# snc98_Display_15x7-Seg_3-digit_LTD056.net
KiCad netlist of a schematic drawn in EAGLE
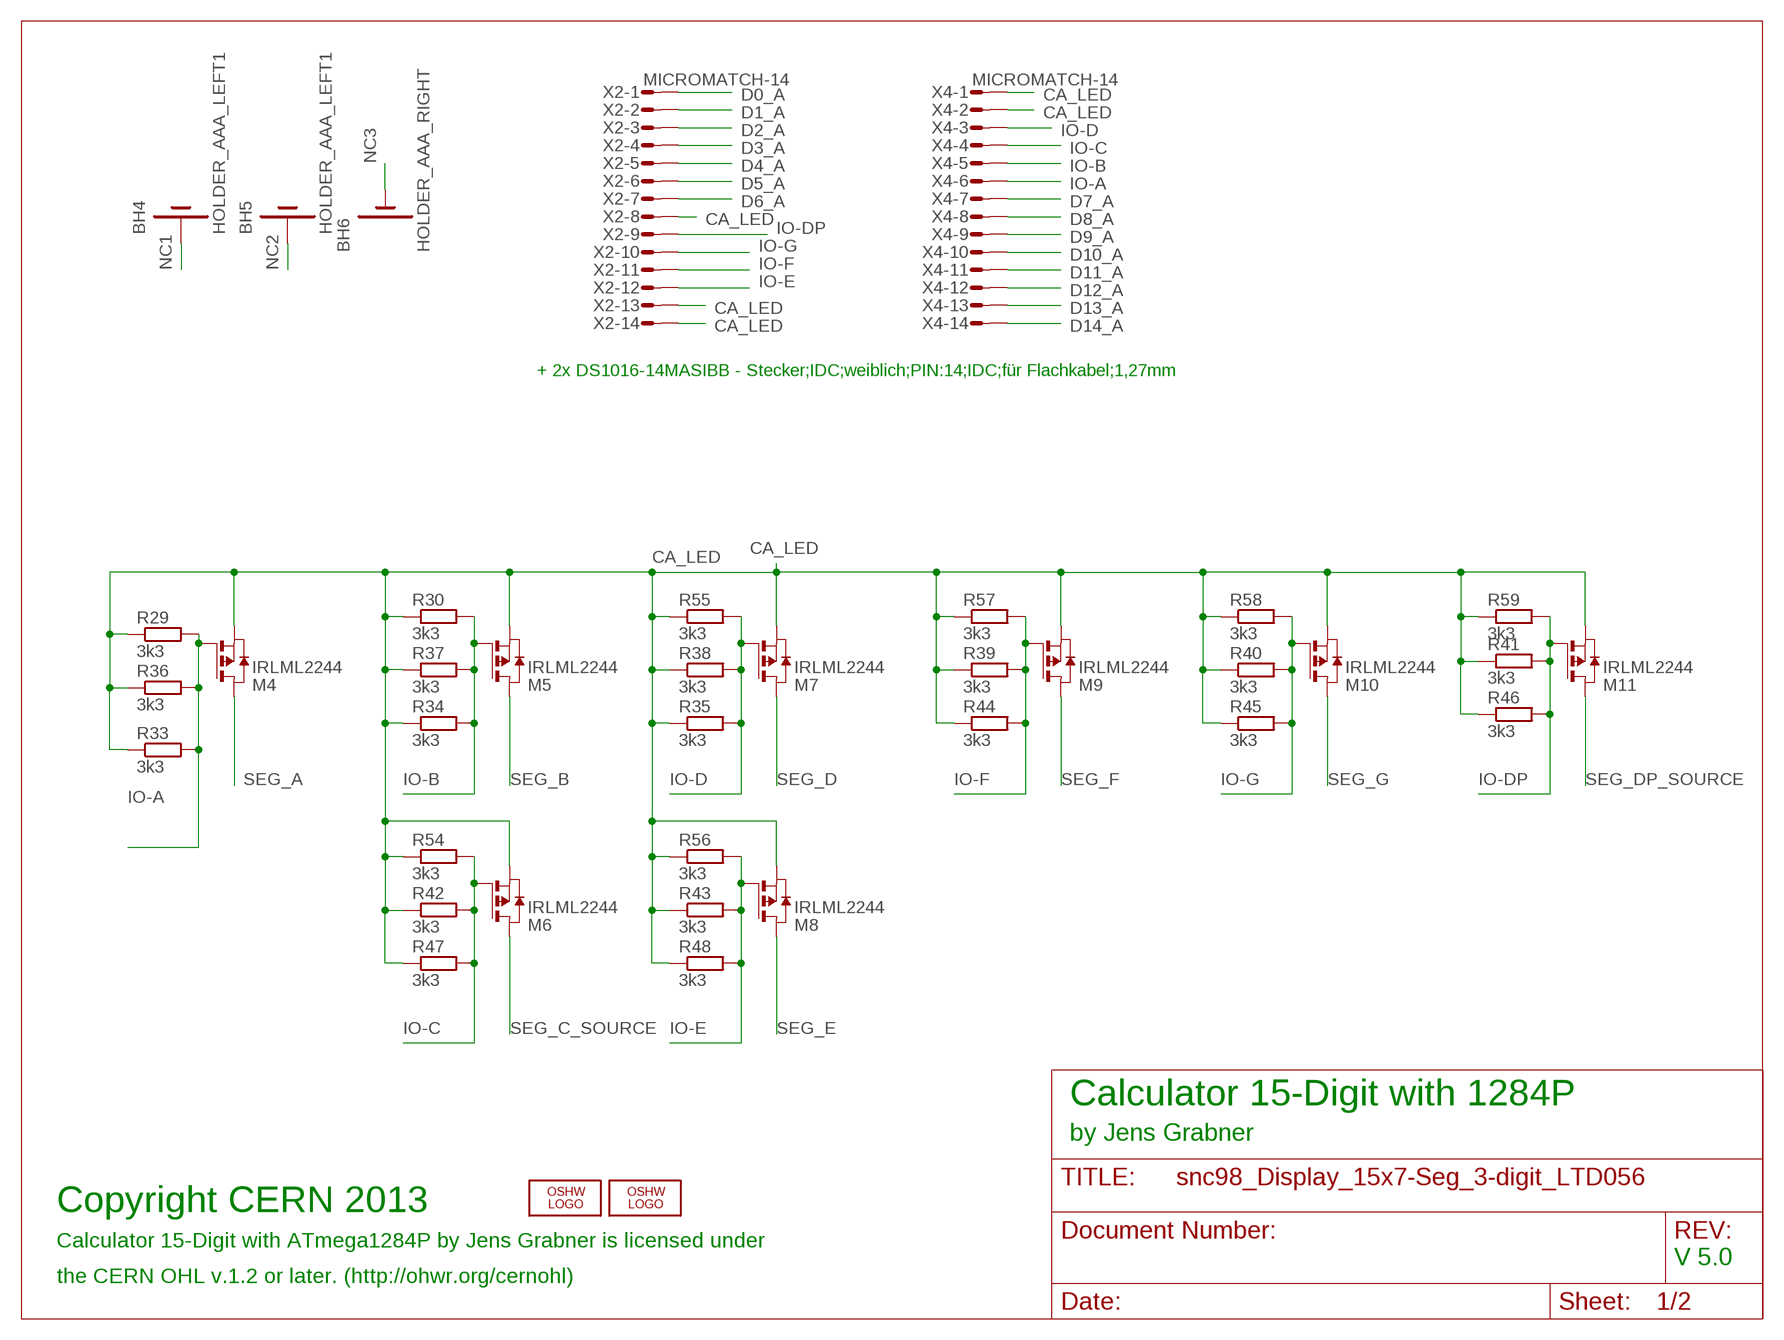
[diagram p0: schematic, sheet 1]
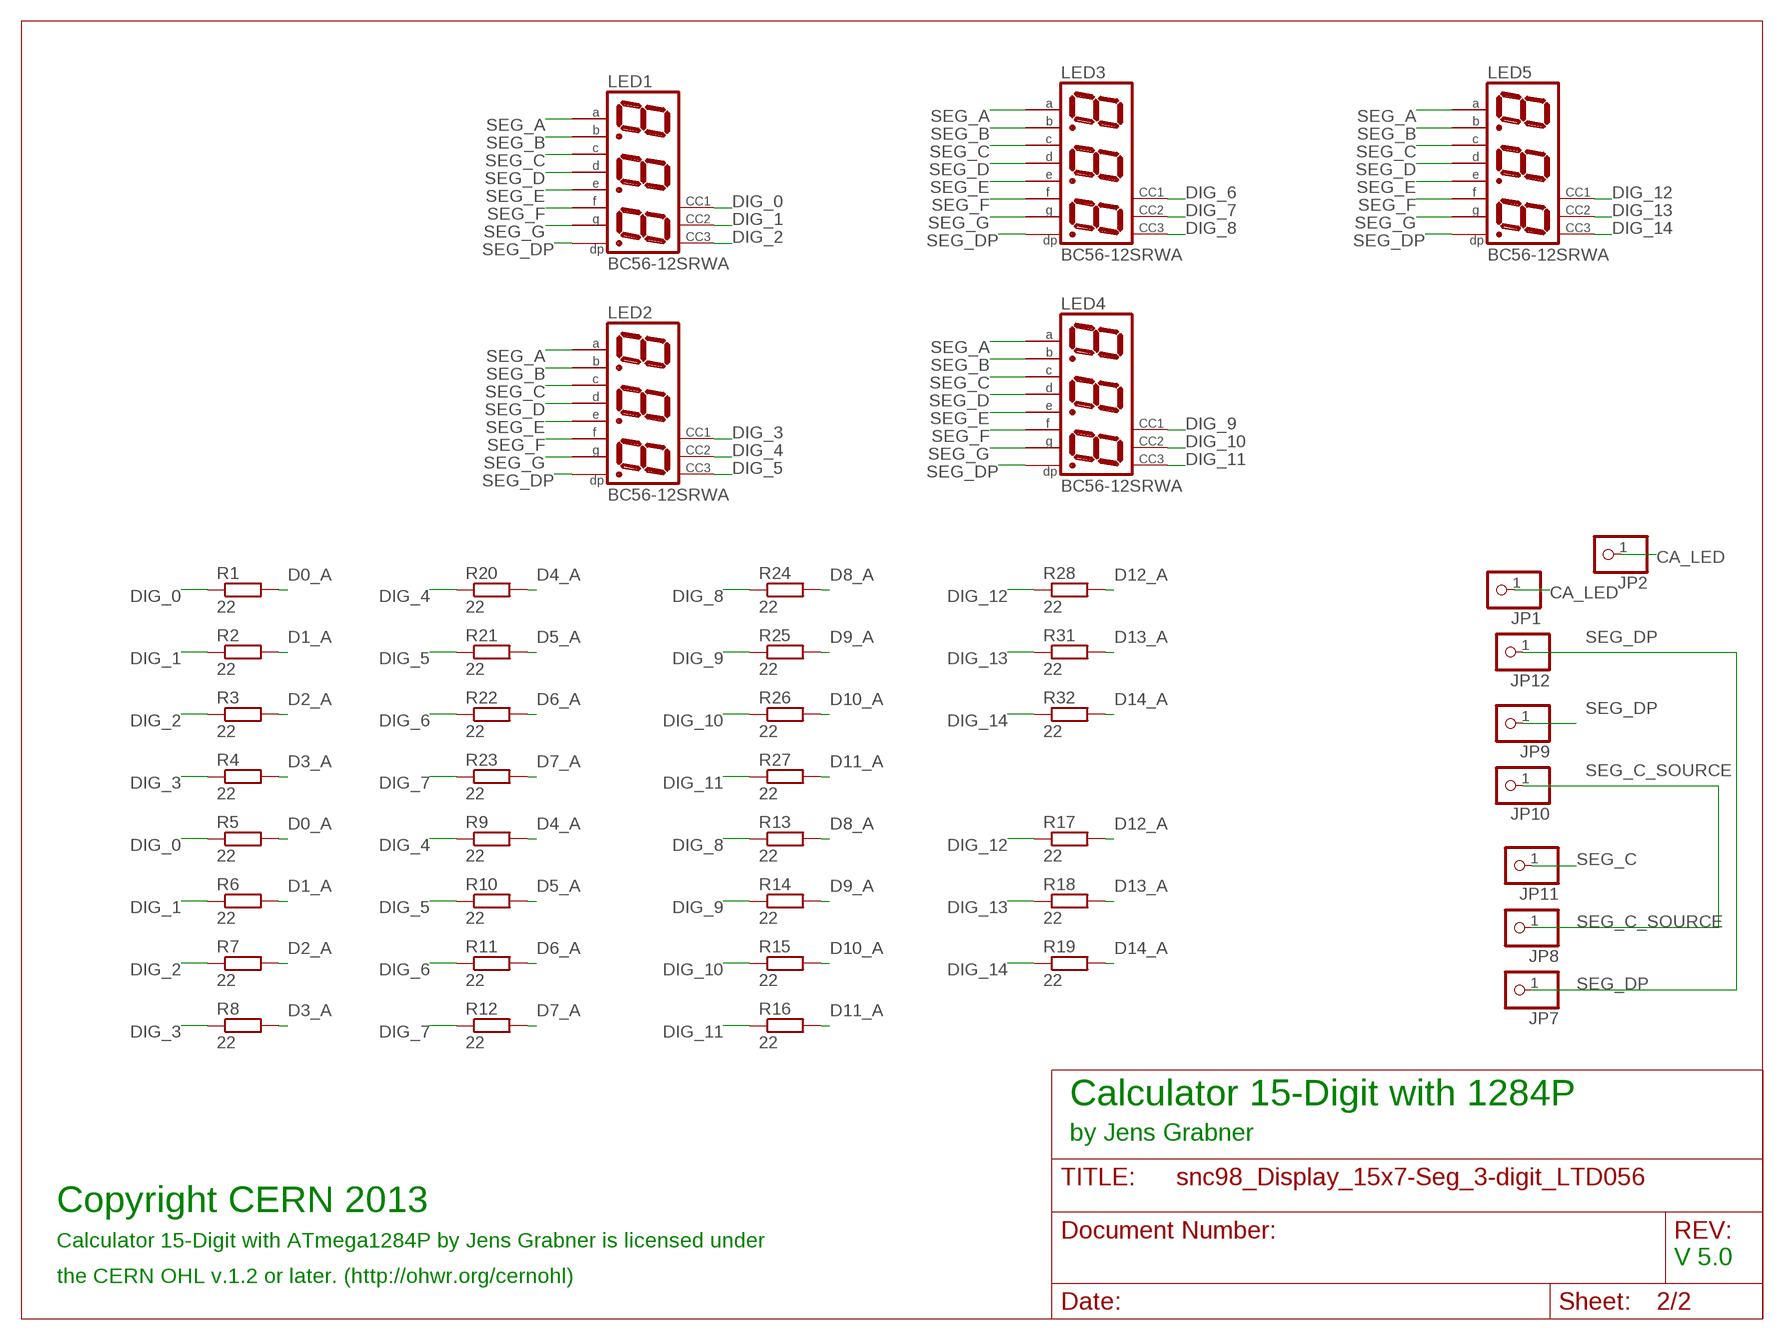
[diagram p1: schematic, sheet 2]

(export (version "E")
  (design (tool "Eeschema 10.0.6"))
  (components
    (comp (ref "JP1")
      (value "PINHD-1X1")
      (footprint "eagle-import:1X01")
      (libsource (lib "eagle-import") (part "PINHD-1X1"))
    )
    (comp (ref "JP2")
      (value "PINHD-1X1")
      (footprint "eagle-import:1X01")
      (libsource (lib "eagle-import") (part "PINHD-1X1"))
    )
    (comp (ref "JP7")
      (value "PINHD-1X1")
      (footprint "eagle-import:1X01")
      (libsource (lib "eagle-import") (part "PINHD-1X1"))
    )
    (comp (ref "JP8")
      (value "PINHD-1X1")
      (footprint "eagle-import:1X01")
      (libsource (lib "eagle-import") (part "PINHD-1X1"))
    )
    (comp (ref "JP9")
      (value "PINHD-1X1")
      (footprint "eagle-import:1X01")
      (libsource (lib "eagle-import") (part "PINHD-1X1"))
    )
    (comp (ref "JP10")
      (value "PINHD-1X1")
      (footprint "eagle-import:1X01")
      (libsource (lib "eagle-import") (part "PINHD-1X1"))
    )
    (comp (ref "JP11")
      (value "PINHD-1X1")
      (footprint "eagle-import:1X01")
      (libsource (lib "eagle-import") (part "PINHD-1X1"))
    )
    (comp (ref "JP12")
      (value "PINHD-1X1")
      (footprint "eagle-import:1X01")
      (libsource (lib "eagle-import") (part "PINHD-1X1"))
    )
    (comp (ref "LED1")
      (value "BC56-12SRWA")
      (footprint "eagle-import:BX56-12")
      (libsource (lib "eagle-import") (part "B?56-12WACSR"))
    )
    (comp (ref "LED2")
      (value "BC56-12SRWA")
      (footprint "eagle-import:BX56-12")
      (libsource (lib "eagle-import") (part "B?56-12WACSR"))
    )
    (comp (ref "LED3")
      (value "BC56-12SRWA")
      (footprint "eagle-import:BX56-12")
      (libsource (lib "eagle-import") (part "B?56-12WACSR"))
    )
    (comp (ref "LED4")
      (value "BC56-12SRWA")
      (footprint "eagle-import:BX56-12")
      (libsource (lib "eagle-import") (part "B?56-12WACSR"))
    )
    (comp (ref "LED5")
      (value "BC56-12SRWA")
      (footprint "eagle-import:BX56-12")
      (libsource (lib "eagle-import") (part "B?56-12WACSR"))
    )
    (comp (ref "R1")
      (value "22")
      (footprint "eagle-import:R0805")
      (libsource (lib "eagle-import") (part "R-EU_R0805"))
    )
    (comp (ref "R2")
      (value "22")
      (footprint "eagle-import:R0805")
      (libsource (lib "eagle-import") (part "R-EU_R0805"))
    )
    (comp (ref "R3")
      (value "22")
      (footprint "eagle-import:R0805")
      (libsource (lib "eagle-import") (part "R-EU_R0805"))
    )
    (comp (ref "R4")
      (value "22")
      (footprint "eagle-import:R0805")
      (libsource (lib "eagle-import") (part "R-EU_R0805"))
    )
    (comp (ref "R5")
      (value "22")
      (footprint "eagle-import:R1210")
      (libsource (lib "eagle-import") (part "R-EU_R1210"))
    )
    (comp (ref "R6")
      (value "22")
      (footprint "eagle-import:R1210")
      (libsource (lib "eagle-import") (part "R-EU_R1210"))
    )
    (comp (ref "R7")
      (value "22")
      (footprint "eagle-import:R1210")
      (libsource (lib "eagle-import") (part "R-EU_R1210"))
    )
    (comp (ref "R8")
      (value "22")
      (footprint "eagle-import:R1210")
      (libsource (lib "eagle-import") (part "R-EU_R1210"))
    )
    (comp (ref "R9")
      (value "22")
      (footprint "eagle-import:R1210")
      (libsource (lib "eagle-import") (part "R-EU_R1210"))
    )
    (comp (ref "R10")
      (value "22")
      (footprint "eagle-import:R1210")
      (libsource (lib "eagle-import") (part "R-EU_R1210"))
    )
    (comp (ref "R11")
      (value "22")
      (footprint "eagle-import:R1210")
      (libsource (lib "eagle-import") (part "R-EU_R1210"))
    )
    (comp (ref "R12")
      (value "22")
      (footprint "eagle-import:R1210")
      (libsource (lib "eagle-import") (part "R-EU_R1210"))
    )
    (comp (ref "R13")
      (value "22")
      (footprint "eagle-import:R1210")
      (libsource (lib "eagle-import") (part "R-EU_R1210"))
    )
    (comp (ref "R14")
      (value "22")
      (footprint "eagle-import:R1210")
      (libsource (lib "eagle-import") (part "R-EU_R1210"))
    )
    (comp (ref "R15")
      (value "22")
      (footprint "eagle-import:R1210")
      (libsource (lib "eagle-import") (part "R-EU_R1210"))
    )
    (comp (ref "R16")
      (value "22")
      (footprint "eagle-import:R1210")
      (libsource (lib "eagle-import") (part "R-EU_R1210"))
    )
    (comp (ref "R17")
      (value "22")
      (footprint "eagle-import:R1210")
      (libsource (lib "eagle-import") (part "R-EU_R1210"))
    )
    (comp (ref "R18")
      (value "22")
      (footprint "eagle-import:R1210")
      (libsource (lib "eagle-import") (part "R-EU_R1210"))
    )
    (comp (ref "R19")
      (value "22")
      (footprint "eagle-import:R1210")
      (libsource (lib "eagle-import") (part "R-EU_R1210"))
    )
    (comp (ref "R20")
      (value "22")
      (footprint "eagle-import:R0805")
      (libsource (lib "eagle-import") (part "R-EU_R0805"))
    )
    (comp (ref "R21")
      (value "22")
      (footprint "eagle-import:R0805")
      (libsource (lib "eagle-import") (part "R-EU_R0805"))
    )
    (comp (ref "R22")
      (value "22")
      (footprint "eagle-import:R0805")
      (libsource (lib "eagle-import") (part "R-EU_R0805"))
    )
    (comp (ref "R23")
      (value "22")
      (footprint "eagle-import:R0805")
      (libsource (lib "eagle-import") (part "R-EU_R0805"))
    )
    (comp (ref "R24")
      (value "22")
      (footprint "eagle-import:R0805")
      (libsource (lib "eagle-import") (part "R-EU_R0805"))
    )
    (comp (ref "R25")
      (value "22")
      (footprint "eagle-import:R0805")
      (libsource (lib "eagle-import") (part "R-EU_R0805"))
    )
    (comp (ref "R26")
      (value "22")
      (footprint "eagle-import:R0805")
      (libsource (lib "eagle-import") (part "R-EU_R0805"))
    )
    (comp (ref "R27")
      (value "22")
      (footprint "eagle-import:R0805")
      (libsource (lib "eagle-import") (part "R-EU_R0805"))
    )
    (comp (ref "R28")
      (value "22")
      (footprint "eagle-import:R0805")
      (libsource (lib "eagle-import") (part "R-EU_R0805"))
    )
    (comp (ref "R31")
      (value "22")
      (footprint "eagle-import:R0805")
      (libsource (lib "eagle-import") (part "R-EU_R0805"))
    )
    (comp (ref "R32")
      (value "22")
      (footprint "eagle-import:R0805")
      (libsource (lib "eagle-import") (part "R-EU_R0805"))
    )
    (comp (ref "BH4")
      (value "HOLDER_AAA_LEFT1")
      (footprint "eagle-import:BATTERY-AAA-LEFT")
      (libsource (lib "eagle-import") (part "HOLDER_AAA_LEFT1"))
    )
    (comp (ref "BH5")
      (value "HOLDER_AAA_LEFT1")
      (footprint "eagle-import:BATTERY-AAA-LEFT")
      (libsource (lib "eagle-import") (part "HOLDER_AAA_LEFT1"))
    )
    (comp (ref "BH6")
      (value "HOLDER_AAA_RIGHT")
      (footprint "eagle-import:BATTERY-AAA-RIGHT")
      (libsource (lib "eagle-import") (part "HOLDER_AAA_RIGHT"))
    )
    (comp (ref "LOGO1")
      (value "OSHW_LOGO_8MILX0150-NT")
      (footprint "eagle-import:OSHW_8X150_NOTEXT")
      (libsource (lib "eagle-import") (part "OSHW_LOGO_8MILX0150-NT"))
    )
    (comp (ref "LOGO3")
      (value "OSHW_LOGO_6MILX0100-NT")
      (footprint "eagle-import:OSHW_6X100_NOTEXT")
      (libsource (lib "eagle-import") (part "OSHW_LOGO_6MILX0100-NT"))
    )
    (comp (ref "M4")
      (value "IRLML2244")
      (footprint "eagle-import:SOT-23")
      (fields (field (name "MF") "INFINEON") (field (name "MPN") "IRLML2244TRPBF"))
      (libsource (lib "eagle-import") (part "IRLML6402"))
    )
    (comp (ref "M5")
      (value "IRLML2244")
      (footprint "eagle-import:SOT-23")
      (fields (field (name "MF") "INFINEON") (field (name "MPN") "IRLML2244TRPBF"))
      (libsource (lib "eagle-import") (part "IRLML6402"))
    )
    (comp (ref "M6")
      (value "IRLML2244")
      (footprint "eagle-import:SOT-23")
      (fields (field (name "MF") "INFINEON") (field (name "MPN") "IRLML2244TRPBF"))
      (libsource (lib "eagle-import") (part "IRLML6402"))
    )
    (comp (ref "M7")
      (value "IRLML2244")
      (footprint "eagle-import:SOT-23")
      (fields (field (name "MF") "INFINEON") (field (name "MPN") "IRLML2244TRPBF"))
      (libsource (lib "eagle-import") (part "IRLML6402"))
    )
    (comp (ref "M8")
      (value "IRLML2244")
      (footprint "eagle-import:SOT-23")
      (fields (field (name "MF") "INFINEON") (field (name "MPN") "IRLML2244TRPBF"))
      (libsource (lib "eagle-import") (part "IRLML6402"))
    )
    (comp (ref "M9")
      (value "IRLML2244")
      (footprint "eagle-import:SOT-23")
      (fields (field (name "MF") "INFINEON") (field (name "MPN") "IRLML2244TRPBF"))
      (libsource (lib "eagle-import") (part "IRLML6402"))
    )
    (comp (ref "M10")
      (value "IRLML2244")
      (footprint "eagle-import:SOT-23")
      (fields (field (name "MF") "INFINEON") (field (name "MPN") "IRLML2244TRPBF"))
      (libsource (lib "eagle-import") (part "IRLML6402"))
    )
    (comp (ref "M11")
      (value "IRLML2244")
      (footprint "eagle-import:SOT-23")
      (fields (field (name "MF") "INFINEON") (field (name "MPN") "IRLML2244TRPBF"))
      (libsource (lib "eagle-import") (part "IRLML6402"))
    )
    (comp (ref "R29")
      (value "3k3")
      (footprint "eagle-import:0204_5")
      (libsource (lib "eagle-import") (part "R-EU_0204/5"))
    )
    (comp (ref "R30")
      (value "3k3")
      (footprint "eagle-import:0204_5")
      (libsource (lib "eagle-import") (part "R-EU_0204/5"))
    )
    (comp (ref "R33")
      (value "3k3")
      (footprint "eagle-import:M0805")
      (libsource (lib "eagle-import") (part "R-EU_M0805"))
    )
    (comp (ref "R34")
      (value "3k3")
      (footprint "eagle-import:M0805")
      (libsource (lib "eagle-import") (part "R-EU_M0805"))
    )
    (comp (ref "R35")
      (value "3k3")
      (footprint "eagle-import:M0805")
      (libsource (lib "eagle-import") (part "R-EU_M0805"))
    )
    (comp (ref "R36")
      (value "3k3")
      (footprint "eagle-import:R1206")
      (libsource (lib "eagle-import") (part "R-EU_R1206"))
    )
    (comp (ref "R37")
      (value "3k3")
      (footprint "eagle-import:R1206")
      (libsource (lib "eagle-import") (part "R-EU_R1206"))
    )
    (comp (ref "R38")
      (value "3k3")
      (footprint "eagle-import:R1206")
      (libsource (lib "eagle-import") (part "R-EU_R1206"))
    )
    (comp (ref "R39")
      (value "3k3")
      (footprint "eagle-import:R1206")
      (libsource (lib "eagle-import") (part "R-EU_R1206"))
    )
    (comp (ref "R40")
      (value "3k3")
      (footprint "eagle-import:R1206")
      (libsource (lib "eagle-import") (part "R-EU_R1206"))
    )
    (comp (ref "R41")
      (value "3k3")
      (footprint "eagle-import:R1206")
      (libsource (lib "eagle-import") (part "R-EU_R1206"))
    )
    (comp (ref "R42")
      (value "3k3")
      (footprint "eagle-import:R1206")
      (libsource (lib "eagle-import") (part "R-EU_R1206"))
    )
    (comp (ref "R43")
      (value "3k3")
      (footprint "eagle-import:R1206")
      (libsource (lib "eagle-import") (part "R-EU_R1206"))
    )
    (comp (ref "R44")
      (value "3k3")
      (footprint "eagle-import:M0805")
      (libsource (lib "eagle-import") (part "R-EU_M0805"))
    )
    (comp (ref "R45")
      (value "3k3")
      (footprint "eagle-import:M0805")
      (libsource (lib "eagle-import") (part "R-EU_M0805"))
    )
    (comp (ref "R46")
      (value "3k3")
      (footprint "eagle-import:M0805")
      (libsource (lib "eagle-import") (part "R-EU_M0805"))
    )
    (comp (ref "R47")
      (value "3k3")
      (footprint "eagle-import:M0805")
      (libsource (lib "eagle-import") (part "R-EU_M0805"))
    )
    (comp (ref "R48")
      (value "3k3")
      (footprint "eagle-import:M0805")
      (libsource (lib "eagle-import") (part "R-EU_M0805"))
    )
    (comp (ref "R54")
      (value "3k3")
      (footprint "eagle-import:0204_5")
      (libsource (lib "eagle-import") (part "R-EU_0204/5"))
    )
    (comp (ref "R55")
      (value "3k3")
      (footprint "eagle-import:0204_5")
      (libsource (lib "eagle-import") (part "R-EU_0204/5"))
    )
    (comp (ref "R56")
      (value "3k3")
      (footprint "eagle-import:0204_5")
      (libsource (lib "eagle-import") (part "R-EU_0204/5"))
    )
    (comp (ref "R57")
      (value "3k3")
      (footprint "eagle-import:0204_5")
      (libsource (lib "eagle-import") (part "R-EU_0204/5"))
    )
    (comp (ref "R58")
      (value "3k3")
      (footprint "eagle-import:0204_5")
      (libsource (lib "eagle-import") (part "R-EU_0204/5"))
    )
    (comp (ref "R59")
      (value "3k3")
      (footprint "eagle-import:0204_5")
      (libsource (lib "eagle-import") (part "R-EU_0204/5"))
    )
    (comp (ref "X2")
      (value "MICROMATCH-14")
      (footprint "eagle-import:MICROMATCH-14")
      (fields
        (field (name "MF") "FARNELL")
        (field (name "MPN") "8-215464-4")
        (field (name "MF_1") "AMP - TE CONNECTIVITY")
      )
      (libsource (lib "eagle-import") (part "MICROMATCH-14"))
    )
    (comp (ref "X4")
      (value "MICROMATCH-14")
      (footprint "eagle-import:MICROMATCH-14")
      (fields
        (field (name "MF") "FARNELL")
        (field (name "MPN") "8-215464-4")
        (field (name "MF_1") "AMP - TE CONNECTIVITY")
      )
      (libsource (lib "eagle-import") (part "MICROMATCH-14"))
    )
  )
  (nets
    (net (code "1") (name "CA_LED") (class "Default")
      (node (ref "JP1") (pin "1") (pinfunction "1_1") (pintype "passive"))
      (node (ref "JP2") (pin "1") (pinfunction "1_1") (pintype "passive"))
      (node (ref "M10") (pin "2") (pinfunction "S_2") (pintype "passive"))
      (node (ref "M11") (pin "2") (pinfunction "S_2") (pintype "passive"))
      (node (ref "M4") (pin "2") (pinfunction "S_2") (pintype "passive"))
      (node (ref "M5") (pin "2") (pinfunction "S_2") (pintype "passive"))
      (node (ref "M6") (pin "2") (pinfunction "S_2") (pintype "passive"))
      (node (ref "M7") (pin "2") (pinfunction "S_2") (pintype "passive"))
      (node (ref "M8") (pin "2") (pinfunction "S_2") (pintype "passive"))
      (node (ref "M9") (pin "2") (pinfunction "S_2") (pintype "passive"))
      (node (ref "R29") (pin "1") (pinfunction "1_1") (pintype "passive"))
      (node (ref "R30") (pin "1") (pinfunction "1_1") (pintype "passive"))
      (node (ref "R33") (pin "1") (pinfunction "1_1") (pintype "passive"))
      (node (ref "R34") (pin "1") (pinfunction "1_1") (pintype "passive"))
      (node (ref "R35") (pin "1") (pinfunction "1_1") (pintype "passive"))
      (node (ref "R36") (pin "1") (pinfunction "1_1") (pintype "passive"))
      (node (ref "R37") (pin "1") (pinfunction "1_1") (pintype "passive"))
      (node (ref "R38") (pin "1") (pinfunction "1_1") (pintype "passive"))
      (node (ref "R39") (pin "1") (pinfunction "1_1") (pintype "passive"))
      (node (ref "R40") (pin "1") (pinfunction "1_1") (pintype "passive"))
      (node (ref "R41") (pin "1") (pinfunction "1_1") (pintype "passive"))
      (node (ref "R42") (pin "1") (pinfunction "1_1") (pintype "passive"))
      (node (ref "R43") (pin "1") (pinfunction "1_1") (pintype "passive"))
      (node (ref "R44") (pin "1") (pinfunction "1_1") (pintype "passive"))
      (node (ref "R45") (pin "1") (pinfunction "1_1") (pintype "passive"))
      (node (ref "R46") (pin "1") (pinfunction "1_1") (pintype "passive"))
      (node (ref "R47") (pin "1") (pinfunction "1_1") (pintype "passive"))
      (node (ref "R48") (pin "1") (pinfunction "1_1") (pintype "passive"))
      (node (ref "R54") (pin "1") (pinfunction "1_1") (pintype "passive"))
      (node (ref "R55") (pin "1") (pinfunction "1_1") (pintype "passive"))
      (node (ref "R56") (pin "1") (pinfunction "1_1") (pintype "passive"))
      (node (ref "R57") (pin "1") (pinfunction "1_1") (pintype "passive"))
      (node (ref "R58") (pin "1") (pinfunction "1_1") (pintype "passive"))
      (node (ref "R59") (pin "1") (pinfunction "1_1") (pintype "passive"))
      (node (ref "X2") (pin "13") (pinfunction "S_13") (pintype "passive"))
      (node (ref "X2") (pin "14") (pinfunction "S_14") (pintype "passive"))
      (node (ref "X2") (pin "8") (pinfunction "S_8") (pintype "passive"))
      (node (ref "X4") (pin "1") (pinfunction "S_1") (pintype "passive"))
      (node (ref "X4") (pin "2") (pinfunction "S_2") (pintype "passive"))
    )
    (net (code "2") (name "D0_A") (class "Default")
      (node (ref "R1") (pin "2") (pinfunction "2_2") (pintype "passive"))
      (node (ref "R5") (pin "2") (pinfunction "2_2") (pintype "passive"))
      (node (ref "X2") (pin "1") (pinfunction "S_1") (pintype "passive"))
    )
    (net (code "3") (name "D1_A") (class "Default")
      (node (ref "R2") (pin "2") (pinfunction "2_2") (pintype "passive"))
      (node (ref "R6") (pin "2") (pinfunction "2_2") (pintype "passive"))
      (node (ref "X2") (pin "2") (pinfunction "S_2") (pintype "passive"))
    )
    (net (code "4") (name "D2_A") (class "Default")
      (node (ref "R3") (pin "2") (pinfunction "2_2") (pintype "passive"))
      (node (ref "R7") (pin "2") (pinfunction "2_2") (pintype "passive"))
      (node (ref "X2") (pin "3") (pinfunction "S_3") (pintype "passive"))
    )
    (net (code "5") (name "D3_A") (class "Default")
      (node (ref "R4") (pin "2") (pinfunction "2_2") (pintype "passive"))
      (node (ref "R8") (pin "2") (pinfunction "2_2") (pintype "passive"))
      (node (ref "X2") (pin "4") (pinfunction "S_4") (pintype "passive"))
    )
    (net (code "6") (name "D4_A") (class "Default")
      (node (ref "R20") (pin "2") (pinfunction "2_2") (pintype "passive"))
      (node (ref "R9") (pin "2") (pinfunction "2_2") (pintype "passive"))
      (node (ref "X2") (pin "5") (pinfunction "S_5") (pintype "passive"))
    )
    (net (code "7") (name "D5_A") (class "Default")
      (node (ref "R10") (pin "2") (pinfunction "2_2") (pintype "passive"))
      (node (ref "R21") (pin "2") (pinfunction "2_2") (pintype "passive"))
      (node (ref "X2") (pin "6") (pinfunction "S_6") (pintype "passive"))
    )
    (net (code "8") (name "D6_A") (class "Default")
      (node (ref "R11") (pin "2") (pinfunction "2_2") (pintype "passive"))
      (node (ref "R22") (pin "2") (pinfunction "2_2") (pintype "passive"))
      (node (ref "X2") (pin "7") (pinfunction "S_7") (pintype "passive"))
    )
    (net (code "9") (name "D7_A") (class "Default")
      (node (ref "R12") (pin "2") (pinfunction "2_2") (pintype "passive"))
      (node (ref "R23") (pin "2") (pinfunction "2_2") (pintype "passive"))
      (node (ref "X4") (pin "7") (pinfunction "S_7") (pintype "passive"))
    )
    (net (code "10") (name "D8_A") (class "Default")
      (node (ref "R13") (pin "2") (pinfunction "2_2") (pintype "passive"))
      (node (ref "R24") (pin "2") (pinfunction "2_2") (pintype "passive"))
      (node (ref "X4") (pin "8") (pinfunction "S_8") (pintype "passive"))
    )
    (net (code "11") (name "D9_A") (class "Default")
      (node (ref "R14") (pin "2") (pinfunction "2_2") (pintype "passive"))
      (node (ref "R25") (pin "2") (pinfunction "2_2") (pintype "passive"))
      (node (ref "X4") (pin "9") (pinfunction "S_9") (pintype "passive"))
    )
    (net (code "12") (name "D10_A") (class "Default")
      (node (ref "R15") (pin "2") (pinfunction "2_2") (pintype "passive"))
      (node (ref "R26") (pin "2") (pinfunction "2_2") (pintype "passive"))
      (node (ref "X4") (pin "10") (pinfunction "S_10") (pintype "passive"))
    )
    (net (code "13") (name "D11_A") (class "Default")
      (node (ref "R16") (pin "2") (pinfunction "2_2") (pintype "passive"))
      (node (ref "R27") (pin "2") (pinfunction "2_2") (pintype "passive"))
      (node (ref "X4") (pin "11") (pinfunction "S_11") (pintype "passive"))
    )
    (net (code "14") (name "D12_A") (class "Default")
      (node (ref "R17") (pin "2") (pinfunction "2_2") (pintype "passive"))
      (node (ref "R28") (pin "2") (pinfunction "2_2") (pintype "passive"))
      (node (ref "X4") (pin "12") (pinfunction "S_12") (pintype "passive"))
    )
    (net (code "15") (name "D13_A") (class "Default")
      (node (ref "R18") (pin "2") (pinfunction "2_2") (pintype "passive"))
      (node (ref "R31") (pin "2") (pinfunction "2_2") (pintype "passive"))
      (node (ref "X4") (pin "13") (pinfunction "S_13") (pintype "passive"))
    )
    (net (code "16") (name "D14_A") (class "Default")
      (node (ref "R19") (pin "2") (pinfunction "2_2") (pintype "passive"))
      (node (ref "R32") (pin "2") (pinfunction "2_2") (pintype "passive"))
      (node (ref "X4") (pin "14") (pinfunction "S_14") (pintype "passive"))
    )
    (net (code "17") (name "DIG_0") (class "Default")
      (node (ref "LED1") (pin "12") (pinfunction "CA_12") (pintype "passive"))
      (node (ref "R1") (pin "1") (pinfunction "1_1") (pintype "passive"))
      (node (ref "R5") (pin "1") (pinfunction "1_1") (pintype "passive"))
    )
    (net (code "18") (name "DIG_1") (class "Default")
      (node (ref "LED1") (pin "9") (pinfunction "CA_9") (pintype "passive"))
      (node (ref "R2") (pin "1") (pinfunction "1_1") (pintype "passive"))
      (node (ref "R6") (pin "1") (pinfunction "1_1") (pintype "passive"))
    )
    (net (code "19") (name "DIG_2") (class "Default")
      (node (ref "LED1") (pin "8") (pinfunction "CA_8") (pintype "passive"))
      (node (ref "R3") (pin "1") (pinfunction "1_1") (pintype "passive"))
      (node (ref "R7") (pin "1") (pinfunction "1_1") (pintype "passive"))
    )
    (net (code "20") (name "DIG_3") (class "Default")
      (node (ref "LED2") (pin "12") (pinfunction "CA_12") (pintype "passive"))
      (node (ref "R4") (pin "1") (pinfunction "1_1") (pintype "passive"))
      (node (ref "R8") (pin "1") (pinfunction "1_1") (pintype "passive"))
    )
    (net (code "21") (name "DIG_4") (class "Default")
      (node (ref "LED2") (pin "9") (pinfunction "CA_9") (pintype "passive"))
      (node (ref "R20") (pin "1") (pinfunction "1_1") (pintype "passive"))
      (node (ref "R9") (pin "1") (pinfunction "1_1") (pintype "passive"))
    )
    (net (code "22") (name "DIG_5") (class "Default")
      (node (ref "LED2") (pin "8") (pinfunction "CA_8") (pintype "passive"))
      (node (ref "R10") (pin "1") (pinfunction "1_1") (pintype "passive"))
      (node (ref "R21") (pin "1") (pinfunction "1_1") (pintype "passive"))
    )
    (net (code "23") (name "DIG_6") (class "Default")
      (node (ref "LED3") (pin "12") (pinfunction "CA_12") (pintype "passive"))
      (node (ref "R11") (pin "1") (pinfunction "1_1") (pintype "passive"))
      (node (ref "R22") (pin "1") (pinfunction "1_1") (pintype "passive"))
    )
    (net (code "24") (name "DIG_7") (class "Default")
      (node (ref "LED3") (pin "9") (pinfunction "CA_9") (pintype "passive"))
      (node (ref "R12") (pin "1") (pinfunction "1_1") (pintype "passive"))
      (node (ref "R23") (pin "1") (pinfunction "1_1") (pintype "passive"))
    )
    (net (code "25") (name "DIG_8") (class "Default")
      (node (ref "LED3") (pin "8") (pinfunction "CA_8") (pintype "passive"))
      (node (ref "R13") (pin "1") (pinfunction "1_1") (pintype "passive"))
      (node (ref "R24") (pin "1") (pinfunction "1_1") (pintype "passive"))
    )
    (net (code "26") (name "DIG_9") (class "Default")
      (node (ref "LED4") (pin "12") (pinfunction "CA_12") (pintype "passive"))
      (node (ref "R14") (pin "1") (pinfunction "1_1") (pintype "passive"))
      (node (ref "R25") (pin "1") (pinfunction "1_1") (pintype "passive"))
    )
    (net (code "27") (name "DIG_10") (class "Default")
      (node (ref "LED4") (pin "9") (pinfunction "CA_9") (pintype "passive"))
      (node (ref "R15") (pin "1") (pinfunction "1_1") (pintype "passive"))
      (node (ref "R26") (pin "1") (pinfunction "1_1") (pintype "passive"))
    )
    (net (code "28") (name "DIG_11") (class "Default")
      (node (ref "LED4") (pin "8") (pinfunction "CA_8") (pintype "passive"))
      (node (ref "R16") (pin "1") (pinfunction "1_1") (pintype "passive"))
      (node (ref "R27") (pin "1") (pinfunction "1_1") (pintype "passive"))
    )
    (net (code "29") (name "DIG_12") (class "Default")
      (node (ref "LED5") (pin "12") (pinfunction "CA_12") (pintype "passive"))
      (node (ref "R17") (pin "1") (pinfunction "1_1") (pintype "passive"))
      (node (ref "R28") (pin "1") (pinfunction "1_1") (pintype "passive"))
    )
    (net (code "30") (name "DIG_13") (class "Default")
      (node (ref "LED5") (pin "9") (pinfunction "CA_9") (pintype "passive"))
      (node (ref "R18") (pin "1") (pinfunction "1_1") (pintype "passive"))
      (node (ref "R31") (pin "1") (pinfunction "1_1") (pintype "passive"))
    )
    (net (code "31") (name "DIG_14") (class "Default")
      (node (ref "LED5") (pin "8") (pinfunction "CA_8") (pintype "passive"))
      (node (ref "R19") (pin "1") (pinfunction "1_1") (pintype "passive"))
      (node (ref "R32") (pin "1") (pinfunction "1_1") (pintype "passive"))
    )
    (net (code "32") (name "IO-A") (class "Default")
      (node (ref "M4") (pin "1") (pinfunction "G_1") (pintype "passive"))
      (node (ref "R29") (pin "2") (pinfunction "2_2") (pintype "passive"))
      (node (ref "R33") (pin "2") (pinfunction "2_2") (pintype "passive"))
      (node (ref "R36") (pin "2") (pinfunction "2_2") (pintype "passive"))
      (node (ref "X4") (pin "6") (pinfunction "S_6") (pintype "passive"))
    )
    (net (code "33") (name "IO-B") (class "Default")
      (node (ref "M5") (pin "1") (pinfunction "G_1") (pintype "passive"))
      (node (ref "R30") (pin "2") (pinfunction "2_2") (pintype "passive"))
      (node (ref "R34") (pin "2") (pinfunction "2_2") (pintype "passive"))
      (node (ref "R37") (pin "2") (pinfunction "2_2") (pintype "passive"))
      (node (ref "X4") (pin "5") (pinfunction "S_5") (pintype "passive"))
    )
    (net (code "34") (name "IO-C") (class "Default")
      (node (ref "M6") (pin "1") (pinfunction "G_1") (pintype "passive"))
      (node (ref "R42") (pin "2") (pinfunction "2_2") (pintype "passive"))
      (node (ref "R47") (pin "2") (pinfunction "2_2") (pintype "passive"))
      (node (ref "R54") (pin "2") (pinfunction "2_2") (pintype "passive"))
      (node (ref "X4") (pin "4") (pinfunction "S_4") (pintype "passive"))
    )
    (net (code "35") (name "IO-D") (class "Default")
      (node (ref "M7") (pin "1") (pinfunction "G_1") (pintype "passive"))
      (node (ref "R35") (pin "2") (pinfunction "2_2") (pintype "passive"))
      (node (ref "R38") (pin "2") (pinfunction "2_2") (pintype "passive"))
      (node (ref "R55") (pin "2") (pinfunction "2_2") (pintype "passive"))
      (node (ref "X4") (pin "3") (pinfunction "S_3") (pintype "passive"))
    )
    (net (code "36") (name "IO-DP") (class "Default")
      (node (ref "M11") (pin "1") (pinfunction "G_1") (pintype "passive"))
      (node (ref "R41") (pin "2") (pinfunction "2_2") (pintype "passive"))
      (node (ref "R46") (pin "2") (pinfunction "2_2") (pintype "passive"))
      (node (ref "R59") (pin "2") (pinfunction "2_2") (pintype "passive"))
      (node (ref "X2") (pin "9") (pinfunction "S_9") (pintype "passive"))
    )
    (net (code "37") (name "IO-E") (class "Default")
      (node (ref "M8") (pin "1") (pinfunction "G_1") (pintype "passive"))
      (node (ref "R43") (pin "2") (pinfunction "2_2") (pintype "passive"))
      (node (ref "R48") (pin "2") (pinfunction "2_2") (pintype "passive"))
      (node (ref "R56") (pin "2") (pinfunction "2_2") (pintype "passive"))
      (node (ref "X2") (pin "12") (pinfunction "S_12") (pintype "passive"))
    )
    (net (code "38") (name "IO-F") (class "Default")
      (node (ref "M9") (pin "1") (pinfunction "G_1") (pintype "passive"))
      (node (ref "R39") (pin "2") (pinfunction "2_2") (pintype "passive"))
      (node (ref "R44") (pin "2") (pinfunction "2_2") (pintype "passive"))
      (node (ref "R57") (pin "2") (pinfunction "2_2") (pintype "passive"))
      (node (ref "X2") (pin "11") (pinfunction "S_11") (pintype "passive"))
    )
    (net (code "39") (name "IO-G") (class "Default")
      (node (ref "M10") (pin "1") (pinfunction "G_1") (pintype "passive"))
      (node (ref "R40") (pin "2") (pinfunction "2_2") (pintype "passive"))
      (node (ref "R45") (pin "2") (pinfunction "2_2") (pintype "passive"))
      (node (ref "R58") (pin "2") (pinfunction "2_2") (pintype "passive"))
      (node (ref "X2") (pin "10") (pinfunction "S_10") (pintype "passive"))
    )
    (net (code "40") (name "NC1") (class "Default")
      (node (ref "BH4") (pin "P1") (pinfunction "+_P1") (pintype "power_in"))
      (node (ref "BH4") (pin "P2") (pinfunction "+_P2") (pintype "power_in"))
      (node (ref "BH4") (pin "P3") (pinfunction "+_P3") (pintype "power_in"))
      (node (ref "BH4") (pin "P4") (pinfunction "+_P4") (pintype "power_in"))
    )
    (net (code "41") (name "NC2") (class "Default")
      (node (ref "BH5") (pin "P1") (pinfunction "+_P1") (pintype "power_in"))
      (node (ref "BH5") (pin "P2") (pinfunction "+_P2") (pintype "power_in"))
      (node (ref "BH5") (pin "P3") (pinfunction "+_P3") (pintype "power_in"))
      (node (ref "BH5") (pin "P4") (pinfunction "+_P4") (pintype "power_in"))
    )
    (net (code "42") (name "NC3") (class "Default")
      (node (ref "BH6") (pin "M1") (pinfunction "-_M1") (pintype "power_in"))
      (node (ref "BH6") (pin "M2") (pinfunction "-_M2") (pintype "power_in"))
      (node (ref "BH6") (pin "M3") (pinfunction "-_M3") (pintype "power_in"))
      (node (ref "BH6") (pin "M4") (pinfunction "-_M4") (pintype "power_in"))
    )
    (net (code "43") (name "SEG_A") (class "Default")
      (node (ref "LED1") (pin "11") (pinfunction "A_11") (pintype "passive"))
      (node (ref "LED2") (pin "11") (pinfunction "A_11") (pintype "passive"))
      (node (ref "LED3") (pin "11") (pinfunction "A_11") (pintype "passive"))
      (node (ref "LED4") (pin "11") (pinfunction "A_11") (pintype "passive"))
      (node (ref "LED5") (pin "11") (pinfunction "A_11") (pintype "passive"))
      (node (ref "M4") (pin "3") (pinfunction "D_3") (pintype "passive"))
    )
    (net (code "44") (name "SEG_B") (class "Default")
      (node (ref "LED1") (pin "7") (pinfunction "B_7") (pintype "passive"))
      (node (ref "LED2") (pin "7") (pinfunction "B_7") (pintype "passive"))
      (node (ref "LED3") (pin "7") (pinfunction "B_7") (pintype "passive"))
      (node (ref "LED4") (pin "7") (pinfunction "B_7") (pintype "passive"))
      (node (ref "LED5") (pin "7") (pinfunction "B_7") (pintype "passive"))
      (node (ref "M5") (pin "3") (pinfunction "D_3") (pintype "passive"))
    )
    (net (code "45") (name "SEG_C") (class "Default")
      (node (ref "JP11") (pin "1") (pinfunction "1_1") (pintype "passive"))
      (node (ref "LED1") (pin "4") (pinfunction "C_4") (pintype "passive"))
      (node (ref "LED2") (pin "4") (pinfunction "C_4") (pintype "passive"))
      (node (ref "LED3") (pin "4") (pinfunction "C_4") (pintype "passive"))
      (node (ref "LED4") (pin "4") (pinfunction "C_4") (pintype "passive"))
      (node (ref "LED5") (pin "4") (pinfunction "C_4") (pintype "passive"))
    )
    (net (code "46") (name "SEG_C_SOURCE") (class "Default")
      (node (ref "JP10") (pin "1") (pinfunction "1_1") (pintype "passive"))
      (node (ref "JP8") (pin "1") (pinfunction "1_1") (pintype "passive"))
      (node (ref "M6") (pin "3") (pinfunction "D_3") (pintype "passive"))
    )
    (net (code "47") (name "SEG_D") (class "Default")
      (node (ref "LED1") (pin "2") (pinfunction "D_2") (pintype "passive"))
      (node (ref "LED2") (pin "2") (pinfunction "D_2") (pintype "passive"))
      (node (ref "LED3") (pin "2") (pinfunction "D_2") (pintype "passive"))
      (node (ref "LED4") (pin "2") (pinfunction "D_2") (pintype "passive"))
      (node (ref "LED5") (pin "2") (pinfunction "D_2") (pintype "passive"))
      (node (ref "M7") (pin "3") (pinfunction "D_3") (pintype "passive"))
    )
    (net (code "48") (name "SEG_DP") (class "Default")
      (node (ref "JP12") (pin "1") (pinfunction "1_1") (pintype "passive"))
      (node (ref "JP7") (pin "1") (pinfunction "1_1") (pintype "passive"))
      (node (ref "JP9") (pin "1") (pinfunction "1_1") (pintype "passive"))
      (node (ref "LED1") (pin "3") (pinfunction "DP_3") (pintype "passive"))
      (node (ref "LED2") (pin "3") (pinfunction "DP_3") (pintype "passive"))
      (node (ref "LED3") (pin "3") (pinfunction "DP_3") (pintype "passive"))
      (node (ref "LED4") (pin "3") (pinfunction "DP_3") (pintype "passive"))
      (node (ref "LED5") (pin "3") (pinfunction "DP_3") (pintype "passive"))
    )
    (net (code "49") (name "SEG_DP_SOURCE") (class "Default")
      (node (ref "M11") (pin "3") (pinfunction "D_3") (pintype "passive"))
    )
    (net (code "50") (name "SEG_E") (class "Default")
      (node (ref "LED1") (pin "1") (pinfunction "E_1") (pintype "passive"))
      (node (ref "LED2") (pin "1") (pinfunction "E_1") (pintype "passive"))
      (node (ref "LED3") (pin "1") (pinfunction "E_1") (pintype "passive"))
      (node (ref "LED4") (pin "1") (pinfunction "E_1") (pintype "passive"))
      (node (ref "LED5") (pin "1") (pinfunction "E_1") (pintype "passive"))
      (node (ref "M8") (pin "3") (pinfunction "D_3") (pintype "passive"))
    )
    (net (code "51") (name "SEG_F") (class "Default")
      (node (ref "LED1") (pin "10") (pinfunction "F_10") (pintype "passive"))
      (node (ref "LED2") (pin "10") (pinfunction "F_10") (pintype "passive"))
      (node (ref "LED3") (pin "10") (pinfunction "F_10") (pintype "passive"))
      (node (ref "LED4") (pin "10") (pinfunction "F_10") (pintype "passive"))
      (node (ref "LED5") (pin "10") (pinfunction "F_10") (pintype "passive"))
      (node (ref "M9") (pin "3") (pinfunction "D_3") (pintype "passive"))
    )
    (net (code "52") (name "SEG_G") (class "Default")
      (node (ref "LED1") (pin "5") (pinfunction "G_5") (pintype "passive"))
      (node (ref "LED2") (pin "5") (pinfunction "G_5") (pintype "passive"))
      (node (ref "LED3") (pin "5") (pinfunction "G_5") (pintype "passive"))
      (node (ref "LED4") (pin "5") (pinfunction "G_5") (pintype "passive"))
      (node (ref "LED5") (pin "5") (pinfunction "G_5") (pintype "passive"))
      (node (ref "M10") (pin "3") (pinfunction "D_3") (pintype "passive"))
    )
  )
)
